# Sheet1.net
KiCad netlist of a schematic drawn in Altium Designer
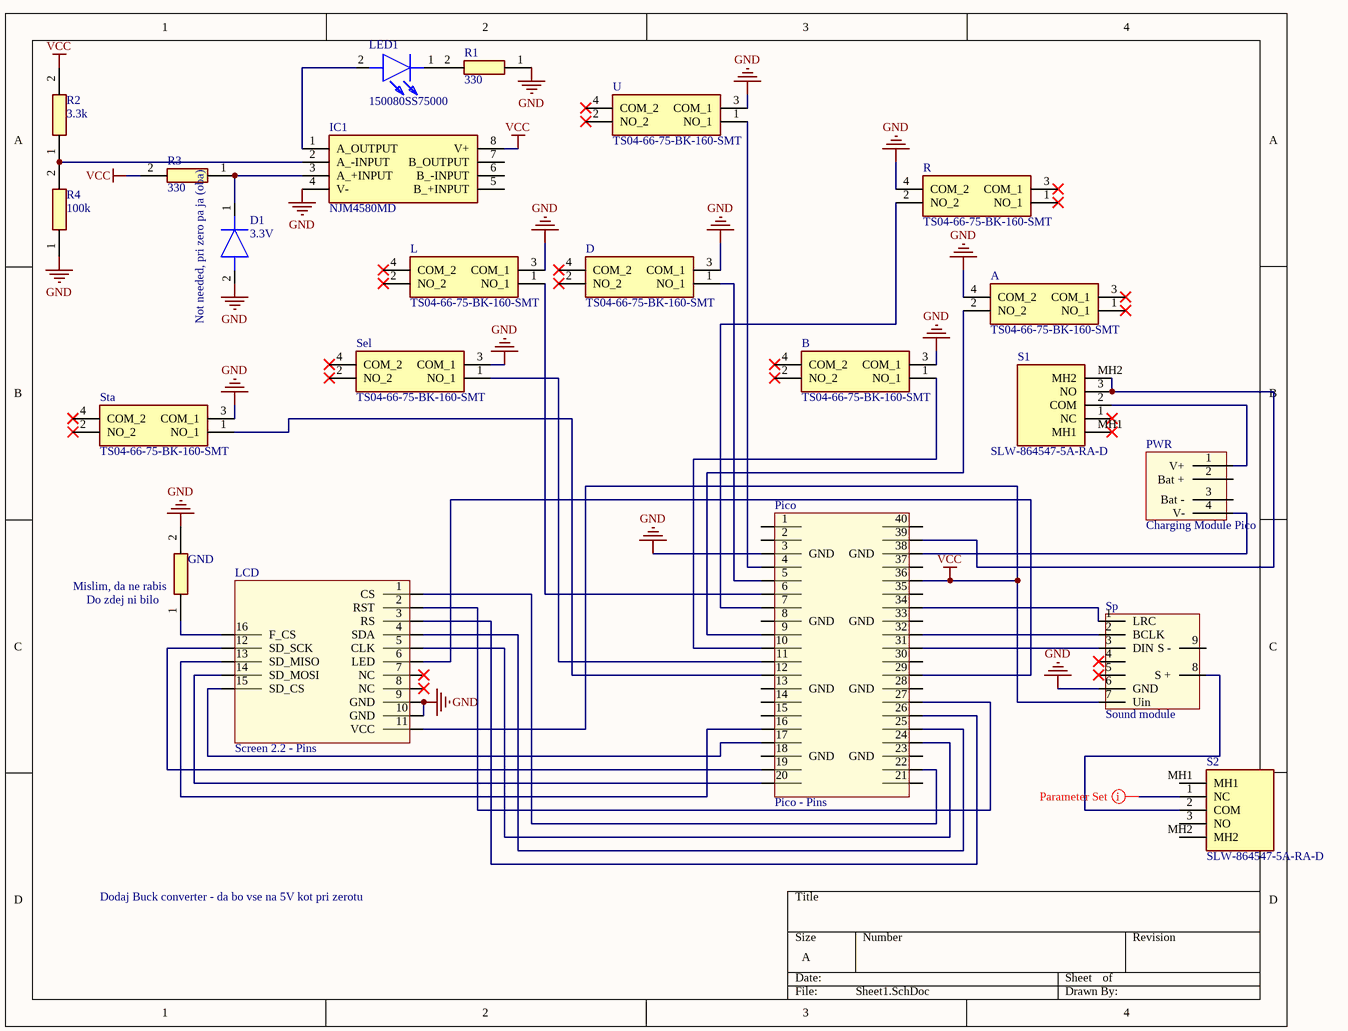
[diagram p0: Sheet1.SchDoc]

(export (version "E")
  (design (tool "Eeschema 10.0.6"))
  (components
    (comp (ref "A")
      (value "TS04-66-75-BK-160-SMT")
      (footprint "SamacSys:TS046675BK160SMT")
      (description "Integrated Circuit")
      (fields (field (name "MOUSER PART NUMBER") "179-TS046675BK160SMT"))
      (libsource (lib "SamacSys") (part "TS04-66-75-BK-160-SMT"))
    )
    (comp (ref "B")
      (value "TS04-66-75-BK-160-SMT")
      (footprint "SamacSys:TS046675BK160SMT")
      (description "Integrated Circuit")
      (fields (field (name "MOUSER PART NUMBER") "179-TS046675BK160SMT"))
      (libsource (lib "SamacSys") (part "TS04-66-75-BK-160-SMT"))
    )
    (comp (ref "D")
      (value "TS04-66-75-BK-160-SMT")
      (footprint "SamacSys:TS046675BK160SMT")
      (description "Integrated Circuit")
      (fields (field (name "MOUSER PART NUMBER") "179-TS046675BK160SMT"))
      (libsource (lib "SamacSys") (part "TS04-66-75-BK-160-SMT"))
    )
    (comp (ref "D1")
      (value "3.3V")
      (footprint "SamacSys:DIOM5027X244N")
      (description "Diode")
      (fields
        (field (name "MANUFACTURER_PART_NUMBER") "1SMA4734-AU_R1_000A1")
        (field (name "MOUSER PART NUMBER") "241-1SMA4734AUR1000A")
      )
      (libsource (lib "*") (part "1SMA4734-AU_R1_000A1"))
    )
    (comp (ref "GND")
      (value "RA73F2A10KBTDF")
      (footprint "SamacSys:RESC2012X58N")
      (description "Resistor")
      (fields (field (name "MOUSER PART NUMBER") "279-RA73F2A10KBTDF"))
      (libsource (lib "SamacSys") (part "RA73F2A10KBTDF"))
    )
    (comp (ref "IC1")
      (value "NJM4580MD")
      (footprint "SamacSys:SOIC127P680X200-8N")
      (description "Integrated Circuit")
      (fields (field (name "MOUSER PART NUMBER") "513-NJM4580MD"))
      (libsource (lib "*") (part "NJM4580MD"))
    )
    (comp (ref "L")
      (value "TS04-66-75-BK-160-SMT")
      (footprint "SamacSys:TS046675BK160SMT")
      (description "Integrated Circuit")
      (fields (field (name "MOUSER PART NUMBER") "179-TS046675BK160SMT"))
      (libsource (lib "SamacSys") (part "TS04-66-75-BK-160-SMT"))
    )
    (comp (ref "LCD")
      (value "Screen 2.2 - Pins")
      (footprint "LCD 2.2''")
      (libsource (lib "Schlib1") (part "Screen 2.2 - Pins"))
    )
    (comp (ref "LED1")
      (value "150080SS75000")
      (footprint "SamacSys:LEDC2012X80N")
      (description "LED")
      (fields (field (name "MOUSER PART NUMBER") "710-150080SS75000"))
      (libsource (lib "SamacSys") (part "150080SS75000"))
    )
    (comp (ref "Pico")
      (value "Pico - Pins")
      (footprint "Pico")
      (libsource (lib "Schlib1") (part "Pico - Pins"))
    )
    (comp (ref "PWR")
      (value "Charging Module Pico")
      (footprint "Charging Module - Pico")
      (libsource (lib "Schlib1") (part "Charging Module Pico"))
    )
    (comp (ref "R")
      (value "TS04-66-75-BK-160-SMT")
      (footprint "SamacSys:TS046675BK160SMT")
      (description "Integrated Circuit")
      (fields (field (name "MOUSER PART NUMBER") "179-TS046675BK160SMT"))
      (libsource (lib "SamacSys") (part "TS04-66-75-BK-160-SMT"))
    )
    (comp (ref "R1")
      (value "330")
      (footprint "SamacSys:RESC3116X75N")
      (description "Resistor")
      (fields
        (field (name "MANUFACTURER_PART_NUMBER") "RQ73C2B10KBTD")
        (field (name "MOUSER PART NUMBER") "279-RQ73C2B10KBTD")
      )
      (libsource (lib "*") (part "RQ73C2B10KBTD"))
    )
    (comp (ref "R2")
      (value "3.3k")
      (footprint "SamacSys:RESC3116X75N")
      (description "Resistor")
      (fields
        (field (name "MANUFACTURER_PART_NUMBER") "RQ73C2B10KBTD")
        (field (name "MOUSER PART NUMBER") "279-RQ73C2B10KBTD")
      )
      (libsource (lib "") (part "RQ73C2B10KBTD_1"))
    )
    (comp (ref "R3")
      (value "330")
      (footprint "SamacSys:RESC3116X75N")
      (description "Resistor")
      (fields
        (field (name "MANUFACTURER_PART_NUMBER") "RQ73C2B10KBTD")
        (field (name "MOUSER PART NUMBER") "279-RQ73C2B10KBTD")
      )
      (libsource (lib "*") (part "RQ73C2B10KBTD"))
    )
    (comp (ref "R4")
      (value "100k")
      (footprint "SamacSys:RESC3116X75N")
      (description "Resistor")
      (fields
        (field (name "MANUFACTURER_PART_NUMBER") "RQ73C2B10KBTD")
        (field (name "MOUSER PART NUMBER") "279-RQ73C2B10KBTD")
      )
      (libsource (lib "") (part "RQ73C2B10KBTD_1"))
    )
    (comp (ref "S1")
      (value "SLW-864547-5A-RA-D")
      (footprint "SamacSys:SLW8645475ARAD")
      (description "Switch")
      (fields (field (name "MOUSER PART NUMBER") "179-SLW-864547-5ARAD"))
      (libsource (lib "*") (part "SLW-864547-5A-RA-D"))
    )
    (comp (ref "S2")
      (value "SLW-864547-5A-RA-D")
      (footprint "SamacSys:SLW8645475ARAD")
      (description "Switch")
      (fields (field (name "MOUSER PART NUMBER") "179-SLW-864547-5ARAD"))
      (libsource (lib "") (part "SLW-864547-5A-RA-D_1"))
    )
    (comp (ref "Sel")
      (value "TS04-66-75-BK-160-SMT")
      (footprint "SamacSys:TS046675BK160SMT")
      (description "Integrated Circuit")
      (fields (field (name "MOUSER PART NUMBER") "179-TS046675BK160SMT"))
      (libsource (lib "SamacSys") (part "TS04-66-75-BK-160-SMT"))
    )
    (comp (ref "Sp")
      (value "Sound module")
      (footprint "Audio module")
      (libsource (lib "Schlib1") (part "Sound module"))
    )
    (comp (ref "Sta")
      (value "TS04-66-75-BK-160-SMT")
      (footprint "SamacSys:TS046675BK160SMT")
      (description "Integrated Circuit")
      (fields (field (name "MOUSER PART NUMBER") "179-TS046675BK160SMT"))
      (libsource (lib "SamacSys") (part "TS04-66-75-BK-160-SMT"))
    )
    (comp (ref "U")
      (value "TS04-66-75-BK-160-SMT")
      (footprint "SamacSys:TS046675BK160SMT")
      (description "Integrated Circuit")
      (fields (field (name "MOUSER PART NUMBER") "179-TS046675BK160SMT"))
      (libsource (lib "SamacSys") (part "TS04-66-75-BK-160-SMT"))
    )
  )
  (nets
    (net (code "1") (name "GND") (class "Default")
      (node (ref "A") (pin "4") (pinfunction "COM_2_4") (pintype "passive"))
      (node (ref "B") (pin "3") (pinfunction "COM_1_3") (pintype "passive"))
      (node (ref "D") (pin "3") (pinfunction "COM_1_3") (pintype "passive"))
      (node (ref "D1") (pin "2") (pinfunction "A_2") (pintype "passive"))
      (node (ref "GND") (pin "2") (pinfunction "2_2") (pintype "passive"))
      (node (ref "IC1") (pin "4") (pinfunction "V-_4") (pintype "passive"))
      (node (ref "L") (pin "3") (pinfunction "COM_1_3") (pintype "passive"))
      (node (ref "LCD") (pin "10") (pinfunction "GND_10") (pintype "passive"))
      (node (ref "LCD") (pin "9") (pinfunction "GND_9") (pintype "passive"))
      (node (ref "Pico") (pin "3") (pinfunction "GND_3") (pintype "passive"))
      (node (ref "R") (pin "4") (pinfunction "COM_2_4") (pintype "passive"))
      (node (ref "R1") (pin "1") (pinfunction "1_1") (pintype "passive"))
      (node (ref "R4") (pin "1") (pinfunction "1_1") (pintype "passive"))
      (node (ref "Sel") (pin "3") (pinfunction "COM_1_3") (pintype "passive"))
      (node (ref "Sp") (pin "6") (pinfunction "GND_6") (pintype "passive"))
      (node (ref "Sta") (pin "3") (pinfunction "COM_1_3") (pintype "passive"))
      (node (ref "U") (pin "3") (pinfunction "COM_1_3") (pintype "passive"))
    )
    (net (code "2") (name "Net-(A-NO_2)") (class "Default")
      (node (ref "A") (pin "2") (pinfunction "NO_2_2") (pintype "passive"))
      (node (ref "Pico") (pin "9") (pinfunction "9_9") (pintype "passive"))
    )
    (net (code "3") (name "Net-(B-NO_1)") (class "Default")
      (node (ref "B") (pin "1") (pinfunction "NO_1_1") (pintype "passive"))
      (node (ref "Pico") (pin "10") (pinfunction "10_10") (pintype "passive"))
    )
    (net (code "4") (name "Net-(D-NO_1)") (class "Default")
      (node (ref "D") (pin "1") (pinfunction "NO_1_1") (pintype "passive"))
      (node (ref "Pico") (pin "5") (pinfunction "5_5") (pintype "passive"))
    )
    (net (code "5") (name "Net-(D1-K)") (class "Default")
      (node (ref "D1") (pin "1") (pinfunction "K_1") (pintype "passive"))
      (node (ref "IC1") (pin "3") (pinfunction "A_+INPUT_3") (pintype "passive"))
      (node (ref "R3") (pin "1") (pinfunction "1_1") (pintype "passive"))
    )
    (net (code "6") (name "Net-(IC1-A_-INPUT)") (class "Default")
      (node (ref "IC1") (pin "2") (pinfunction "A_-INPUT_2") (pintype "passive"))
      (node (ref "R2") (pin "1") (pinfunction "1_1") (pintype "passive"))
      (node (ref "R4") (pin "2") (pinfunction "2_2") (pintype "passive"))
    )
    (net (code "7") (name "Net-(IC1-A_OUTPUT)") (class "Default")
      (node (ref "IC1") (pin "1") (pinfunction "A_OUTPUT_1") (pintype "passive"))
      (node (ref "LED1") (pin "2") (pinfunction "A_2") (pintype "passive"))
    )
    (net (code "8") (name "Net-(L-NO_1)") (class "Default")
      (node (ref "L") (pin "1") (pinfunction "NO_1_1") (pintype "passive"))
      (node (ref "Pico") (pin "6") (pinfunction "6_6") (pintype "passive"))
    )
    (net (code "9") (name "Net-(LCD-CLK)") (class "Default")
      (node (ref "LCD") (pin "5") (pinfunction "CLK_5") (pintype "passive"))
      (node (ref "Pico") (pin "24") (pinfunction "37_24") (pintype "passive"))
    )
    (net (code "10") (name "Net-(LCD-CS)") (class "Default")
      (node (ref "LCD") (pin "1") (pinfunction "CS_1") (pintype "passive"))
      (node (ref "Pico") (pin "22") (pinfunction "39_22") (pintype "passive"))
    )
    (net (code "11") (name "Net-(LCD-F_CS)") (class "Default")
      (node (ref "GND") (pin "1") (pinfunction "1_1") (pintype "passive"))
      (node (ref "LCD") (pin "16") (pinfunction "F_CS_16") (pintype "passive"))
    )
    (net (code "12") (name "Net-(LCD-LED)") (class "Default")
      (node (ref "LCD") (pin "6") (pinfunction "LED_6") (pintype "passive"))
      (node (ref "Pico") (pin "29") (pinfunction "32_29") (pintype "passive"))
    )
    (net (code "13") (name "Net-(LCD-RS)") (class "Default")
      (node (ref "LCD") (pin "3") (pinfunction "RS_3") (pintype "passive"))
      (node (ref "Pico") (pin "26") (pinfunction "35_26") (pintype "passive"))
    )
    (net (code "14") (name "Net-(LCD-RST)") (class "Default")
      (node (ref "LCD") (pin "2") (pinfunction "RST_2") (pintype "passive"))
      (node (ref "Pico") (pin "27") (pinfunction "34_27") (pintype "passive"))
    )
    (net (code "15") (name "Net-(LCD-SDA)") (class "Default")
      (node (ref "LCD") (pin "4") (pinfunction "SDA_4") (pintype "passive"))
      (node (ref "Pico") (pin "25") (pinfunction "36_25") (pintype "passive"))
    )
    (net (code "16") (name "Net-(LCD-SD_CS)") (class "Default")
      (node (ref "LCD") (pin "15") (pinfunction "SD_CS_15") (pintype "passive"))
      (node (ref "Pico") (pin "17") (pinfunction "17_17") (pintype "passive"))
    )
    (net (code "17") (name "Net-(LCD-SD_MISO)") (class "Default")
      (node (ref "LCD") (pin "13") (pinfunction "SD_MISO_13") (pintype "passive"))
      (node (ref "Pico") (pin "16") (pinfunction "16_16") (pintype "passive"))
    )
    (net (code "18") (name "Net-(LCD-SD_MOSI)") (class "Default")
      (node (ref "LCD") (pin "14") (pinfunction "SD_MOSI_14") (pintype "passive"))
      (node (ref "Pico") (pin "20") (pinfunction "20_20") (pintype "passive"))
    )
    (net (code "19") (name "Net-(LCD-SD_SCK)") (class "Default")
      (node (ref "LCD") (pin "12") (pinfunction "SD_SCK_12") (pintype "passive"))
      (node (ref "Pico") (pin "19") (pinfunction "19_19") (pintype "passive"))
    )
    (net (code "20") (name "Net-(LED1-K)") (class "Default")
      (node (ref "LED1") (pin "1") (pinfunction "K_1") (pintype "passive"))
      (node (ref "R1") (pin "2") (pinfunction "2_2") (pintype "passive"))
    )
    (net (code "21") (name "Net-(PWR-V+)") (class "Default")
      (node (ref "PWR") (pin "1") (pinfunction "V+_1") (pintype "passive"))
      (node (ref "S1") (pin "2") (pinfunction "COM_2") (pintype "passive"))
    )
    (net (code "22") (name "Net-(PWR-V-)") (class "Default")
      (node (ref "PWR") (pin "4") (pinfunction "V-_4") (pintype "passive"))
      (node (ref "Pico") (pin "38") (pinfunction "GND_38") (pintype "passive"))
    )
    (net (code "23") (name "Net-(Pico-27)") (class "Default")
      (node (ref "Pico") (pin "34") (pinfunction "27_34") (pintype "passive"))
      (node (ref "Sp") (pin "1") (pinfunction "LRC_1") (pintype "passive"))
    )
    (net (code "24") (name "Net-(Pico-29)") (class "Default")
      (node (ref "Pico") (pin "32") (pinfunction "29_32") (pintype "passive"))
      (node (ref "Sp") (pin "2") (pinfunction "BCLK_2") (pintype "passive"))
    )
    (net (code "25") (name "Net-(Pico-30)") (class "Default")
      (node (ref "Pico") (pin "31") (pinfunction "30_31") (pintype "passive"))
      (node (ref "Sp") (pin "3") (pinfunction "DIN_3") (pintype "passive"))
    )
    (net (code "26") (name "Net-(R-NO_2)") (class "Default")
      (node (ref "Pico") (pin "7") (pinfunction "7_7") (pintype "passive"))
      (node (ref "R") (pin "2") (pinfunction "NO_2_2") (pintype "passive"))
    )
    (net (code "27") (name "Net-(S1-NO)") (class "Default")
      (node (ref "Pico") (pin "39") (pinfunction "22_39") (pintype "passive"))
      (node (ref "S1") (pin "3") (pinfunction "NO_3") (pintype "passive"))
      (node (ref "S1") (pin "MH2") (pinfunction "MH2_MH2") (pintype "passive"))
    )
    (net (code "28") (name "Net-(S2-COM)") (class "Default")
      (node (ref "S2") (pin "2") (pinfunction "COM_2") (pintype "passive"))
      (node (ref "Sp") (pin "8") (pinfunction "S_+_8") (pintype "passive"))
    )
    (net (code "29") (name "Net-(Sel-NO_1)") (class "Default")
      (node (ref "Pico") (pin "11") (pinfunction "11_11") (pintype "passive"))
      (node (ref "Sel") (pin "1") (pinfunction "NO_1_1") (pintype "passive"))
    )
    (net (code "30") (name "Net-(Sta-NO_1)") (class "Default")
      (node (ref "Pico") (pin "12") (pinfunction "12_12") (pintype "passive"))
      (node (ref "Sta") (pin "1") (pinfunction "NO_1_1") (pintype "passive"))
    )
    (net (code "31") (name "Net-(U-NO_1)") (class "Default")
      (node (ref "Pico") (pin "4") (pinfunction "4_4") (pintype "passive"))
      (node (ref "U") (pin "1") (pinfunction "NO_1_1") (pintype "passive"))
    )
    (net (code "32") (name "VCC") (class "Default")
      (node (ref "IC1") (pin "8") (pinfunction "V+_8") (pintype "passive"))
      (node (ref "LCD") (pin "11") (pinfunction "VCC_11") (pintype "passive"))
      (node (ref "Pico") (pin "36") (pinfunction "25_36") (pintype "passive"))
      (node (ref "R2") (pin "2") (pinfunction "2_2") (pintype "passive"))
      (node (ref "R3") (pin "2") (pinfunction "2_2") (pintype "passive"))
      (node (ref "Sp") (pin "7") (pinfunction "Uin_7") (pintype "passive"))
    )
    (net (code "33") (name "unconnected-(A-COM_1-Pad3)") (class "Default")
      (node (ref "A") (pin "3") (pinfunction "COM_1_3") (pintype "passive+no_connect"))
    )
    (net (code "34") (name "unconnected-(A-NO_1-Pad1)") (class "Default")
      (node (ref "A") (pin "1") (pinfunction "NO_1_1") (pintype "passive+no_connect"))
    )
    (net (code "35") (name "unconnected-(B-COM_2-Pad4)") (class "Default")
      (node (ref "B") (pin "4") (pinfunction "COM_2_4") (pintype "passive+no_connect"))
    )
    (net (code "36") (name "unconnected-(B-NO_2-Pad2)") (class "Default")
      (node (ref "B") (pin "2") (pinfunction "NO_2_2") (pintype "passive+no_connect"))
    )
    (net (code "37") (name "unconnected-(D-COM_2-Pad4)") (class "Default")
      (node (ref "D") (pin "4") (pinfunction "COM_2_4") (pintype "passive+no_connect"))
    )
    (net (code "38") (name "unconnected-(D-NO_2-Pad2)") (class "Default")
      (node (ref "D") (pin "2") (pinfunction "NO_2_2") (pintype "passive+no_connect"))
    )
    (net (code "39") (name "unconnected-(IC1-B_+INPUT-Pad5)") (class "Default")
      (node (ref "IC1") (pin "5") (pinfunction "B_+INPUT_5") (pintype "passive"))
    )
    (net (code "40") (name "unconnected-(IC1-B_-INPUT-Pad6)") (class "Default")
      (node (ref "IC1") (pin "6") (pinfunction "B_-INPUT_6") (pintype "passive"))
    )
    (net (code "41") (name "unconnected-(IC1-B_OUTPUT-Pad7)") (class "Default")
      (node (ref "IC1") (pin "7") (pinfunction "B_OUTPUT_7") (pintype "passive"))
    )
    (net (code "42") (name "unconnected-(L-COM_2-Pad4)") (class "Default")
      (node (ref "L") (pin "4") (pinfunction "COM_2_4") (pintype "passive+no_connect"))
    )
    (net (code "43") (name "unconnected-(L-NO_2-Pad2)") (class "Default")
      (node (ref "L") (pin "2") (pinfunction "NO_2_2") (pintype "passive+no_connect"))
    )
    (net (code "44") (name "unconnected-(LCD-NC-Pad7)") (class "Default")
      (node (ref "LCD") (pin "7") (pinfunction "NC_7") (pintype "passive+no_connect"))
    )
    (net (code "45") (name "unconnected-(LCD-NC-Pad8)") (class "Default")
      (node (ref "LCD") (pin "8") (pinfunction "NC_8") (pintype "passive+no_connect"))
    )
    (net (code "46") (name "unconnected-(PWR-Bat_+-Pad2)") (class "Default")
      (node (ref "PWR") (pin "2") (pinfunction "Bat_+_2") (pintype "passive"))
    )
    (net (code "47") (name "unconnected-(PWR-Bat_--Pad3)") (class "Default")
      (node (ref "PWR") (pin "3") (pinfunction "Bat_-_3") (pintype "passive"))
    )
    (net (code "48") (name "unconnected-(Pico-21-Pad40)") (class "Default")
      (node (ref "Pico") (pin "40") (pinfunction "21_40") (pintype "passive"))
    )
    (net (code "49") (name "unconnected-(Pico-22-Pad1)") (class "Default")
      (node (ref "Pico") (pin "1") (pinfunction "22_1") (pintype "passive"))
    )
    (net (code "50") (name "unconnected-(Pico-24-Pad37)") (class "Default")
      (node (ref "Pico") (pin "37") (pinfunction "24_37") (pintype "passive"))
    )
    (net (code "51") (name "unconnected-(Pico-26-Pad35)") (class "Default")
      (node (ref "Pico") (pin "35") (pinfunction "26_35") (pintype "passive"))
    )
    (net (code "52") (name "unconnected-(Pico-31-Pad30)") (class "Default")
      (node (ref "Pico") (pin "30") (pinfunction "31_30") (pintype "passive"))
    )
    (net (code "53") (name "unconnected-(Pico-40-Pad21)") (class "Default")
      (node (ref "Pico") (pin "21") (pinfunction "40_21") (pintype "passive"))
    )
    (net (code "54") (name "unconnected-(Pico-GND-Pad8)") (class "Default")
      (node (ref "Pico") (pin "8") (pinfunction "GND_8") (pintype "passive"))
    )
    (net (code "55") (name "unconnected-(Pico-GND-Pad13)") (class "Default")
      (node (ref "Pico") (pin "13") (pinfunction "GND_13") (pintype "passive"))
    )
    (net (code "56") (name "unconnected-(Pico-GND-Pad18)") (class "Default")
      (node (ref "Pico") (pin "18") (pinfunction "GND_18") (pintype "passive"))
    )
    (net (code "57") (name "unconnected-(Pico-GND-Pad23)") (class "Default")
      (node (ref "Pico") (pin "23") (pinfunction "GND_23") (pintype "passive"))
    )
    (net (code "58") (name "unconnected-(Pico-GND-Pad28)") (class "Default")
      (node (ref "Pico") (pin "28") (pinfunction "GND_28") (pintype "passive"))
    )
    (net (code "59") (name "unconnected-(Pico-GND-Pad33)") (class "Default")
      (node (ref "Pico") (pin "33") (pinfunction "GND_33") (pintype "passive"))
    )
    (net (code "60") (name "unconnected-(Pico-Pad2)") (class "Default")
      (node (ref "Pico") (pin "2") (pinfunction "2_2") (pintype "passive"))
    )
    (net (code "61") (name "unconnected-(Pico-Pad14)") (class "Default")
      (node (ref "Pico") (pin "14") (pinfunction "14_14") (pintype "passive"))
    )
    (net (code "62") (name "unconnected-(Pico-Pad15)") (class "Default")
      (node (ref "Pico") (pin "15") (pinfunction "15_15") (pintype "passive"))
    )
    (net (code "63") (name "unconnected-(R-COM_1-Pad3)") (class "Default")
      (node (ref "R") (pin "3") (pinfunction "COM_1_3") (pintype "passive+no_connect"))
    )
    (net (code "64") (name "unconnected-(R-NO_1-Pad1)") (class "Default")
      (node (ref "R") (pin "1") (pinfunction "NO_1_1") (pintype "passive+no_connect"))
    )
    (net (code "65") (name "unconnected-(S1-NC-Pad1)") (class "Default")
      (node (ref "S1") (pin "1") (pinfunction "NC_1") (pintype "passive+no_connect"))
    )
    (net (code "66") (name "unconnected-(S1-PadMH1)") (class "Default")
      (node (ref "S1") (pin "MH1") (pinfunction "MH1_MH1") (pintype "passive+no_connect"))
    )
    (net (code "67") (name "unconnected-(S2-NC-Pad1)") (class "Default")
      (node (ref "S2") (pin "1") (pinfunction "NC_1") (pintype "passive"))
    )
    (net (code "68") (name "unconnected-(S2-NO-Pad3)") (class "Default")
      (node (ref "S2") (pin "3") (pinfunction "NO_3") (pintype "passive"))
    )
    (net (code "69") (name "unconnected-(S2-PadMH1)") (class "Default")
      (node (ref "S2") (pin "MH1") (pinfunction "MH1_MH1") (pintype "passive"))
    )
    (net (code "70") (name "unconnected-(S2-PadMH2)") (class "Default")
      (node (ref "S2") (pin "MH2") (pinfunction "MH2_MH2") (pintype "passive"))
    )
    (net (code "71") (name "unconnected-(Sel-COM_2-Pad4)") (class "Default")
      (node (ref "Sel") (pin "4") (pinfunction "COM_2_4") (pintype "passive+no_connect"))
    )
    (net (code "72") (name "unconnected-(Sel-NO_2-Pad2)") (class "Default")
      (node (ref "Sel") (pin "2") (pinfunction "NO_2_2") (pintype "passive+no_connect"))
    )
    (net (code "73") (name "unconnected-(Sp-17-Pad4)") (class "Default")
      (node (ref "Sp") (pin "4") (pinfunction "17_4") (pintype "passive+no_connect"))
    )
    (net (code "74") (name "unconnected-(Sp-17-Pad5)") (class "Default")
      (node (ref "Sp") (pin "5") (pinfunction "17_5") (pintype "passive+no_connect"))
    )
    (net (code "75") (name "unconnected-(Sp-S_--Pad9)") (class "Default")
      (node (ref "Sp") (pin "9") (pinfunction "S_-_9") (pintype "passive"))
    )
    (net (code "76") (name "unconnected-(Sta-COM_2-Pad4)") (class "Default")
      (node (ref "Sta") (pin "4") (pinfunction "COM_2_4") (pintype "passive+no_connect"))
    )
    (net (code "77") (name "unconnected-(Sta-NO_2-Pad2)") (class "Default")
      (node (ref "Sta") (pin "2") (pinfunction "NO_2_2") (pintype "passive+no_connect"))
    )
    (net (code "78") (name "unconnected-(U-COM_2-Pad4)") (class "Default")
      (node (ref "U") (pin "4") (pinfunction "COM_2_4") (pintype "passive+no_connect"))
    )
    (net (code "79") (name "unconnected-(U-NO_2-Pad2)") (class "Default")
      (node (ref "U") (pin "2") (pinfunction "NO_2_2") (pintype "passive+no_connect"))
    )
  )
)
